# misc_rf.net
KiCad netlist of a schematic drawn in Altium Designer
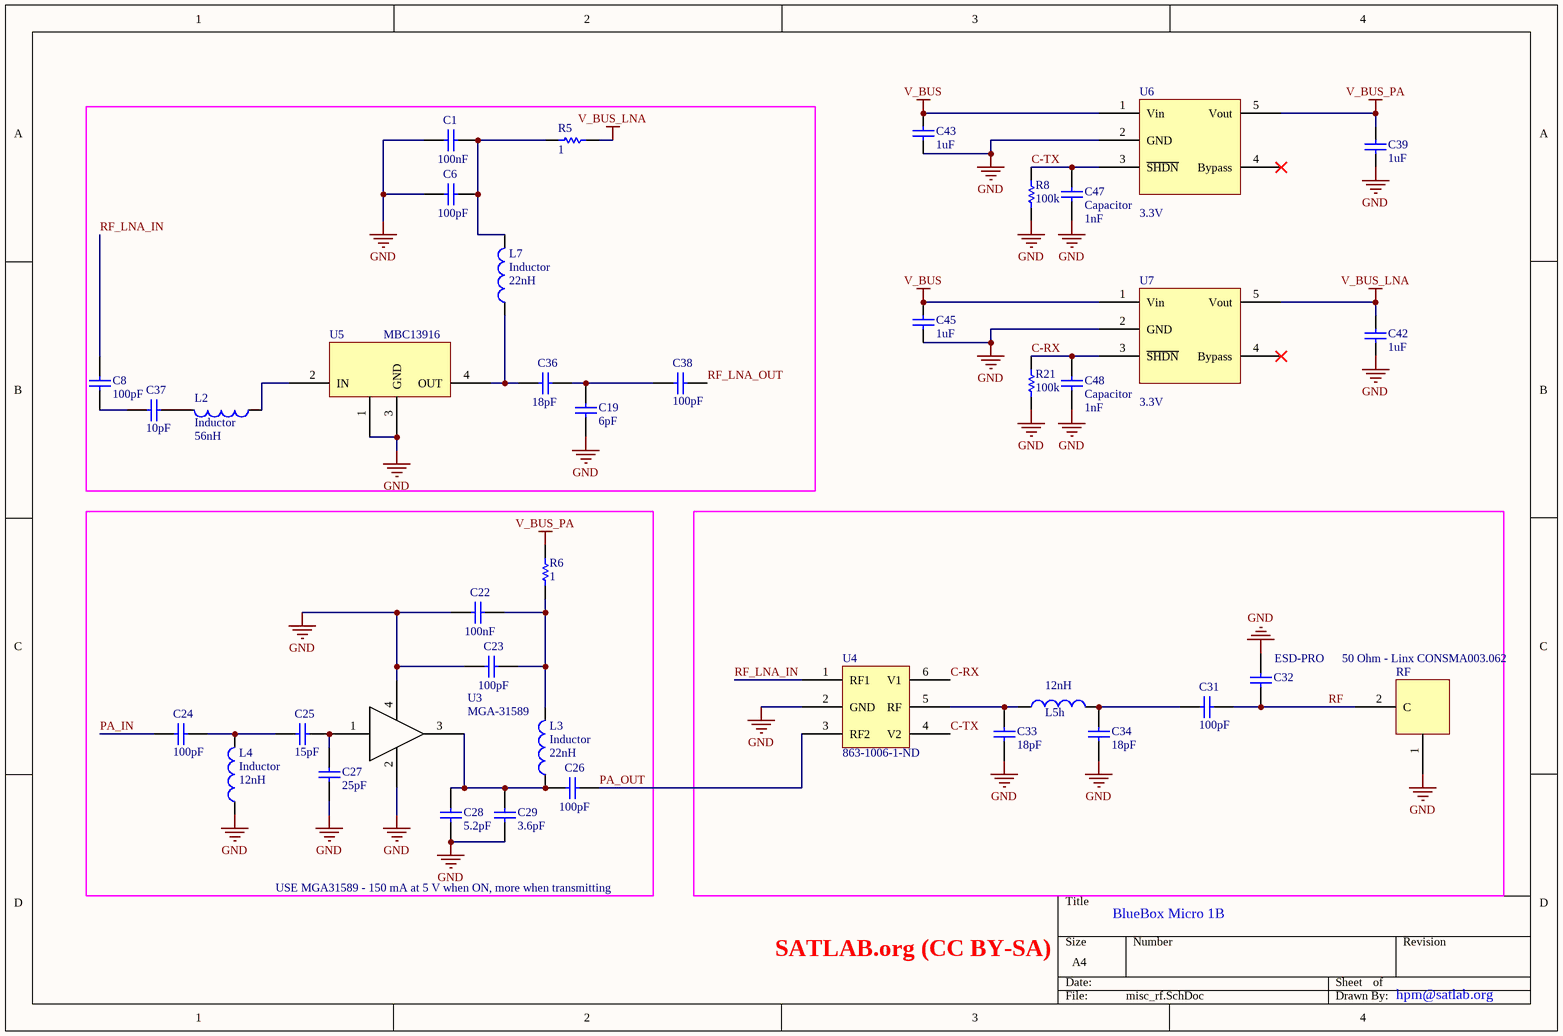
[diagram p0: misc_rf.SchDoc]

(export (version "E")
  (design (tool "Eeschema 10.0.6"))
  (components
    (comp (ref "C1")
      (value "100nF")
      (footprint "C06")
      (description "Capacitor (Semiconductor SIM Model)")
      (fields (field (name "Comment") "Cap Semi") (field (name "PUBLISHER") "Altium Limited"))
      (libsource (lib "common") (part "Capacitor"))
    )
    (comp (ref "C6")
      (value "100pF")
      (footprint "C06")
      (description "Capacitor (Semiconductor SIM Model)")
      (fields (field (name "Comment") "Cap Semi") (field (name "PUBLISHER") "Altium Limited"))
      (libsource (lib "common") (part "Capacitor"))
    )
    (comp (ref "C8")
      (value "100pF")
      (footprint "C06")
      (description "Capacitor (Semiconductor SIM Model)")
      (fields (field (name "Comment") "Cap Semi") (field (name "PUBLISHER") "Altium Limited"))
      (libsource (lib "common") (part "Capacitor"))
    )
    (comp (ref "C19")
      (value "6pF")
      (footprint "C06")
      (description "Capacitor (Semiconductor SIM Model)")
      (fields (field (name "Comment") "Cap Semi") (field (name "PUBLISHER") "Altium Limited"))
      (libsource (lib "common") (part "Capacitor"))
    )
    (comp (ref "C22")
      (value "100nF")
      (footprint "C06")
      (description "Capacitor (Semiconductor SIM Model)")
      (fields (field (name "Comment") "Cap Semi") (field (name "PUBLISHER") "Altium Limited"))
      (libsource (lib "common") (part "Capacitor"))
    )
    (comp (ref "C23")
      (value "100pF")
      (footprint "C06")
      (description "Capacitor (Semiconductor SIM Model)")
      (fields (field (name "Comment") "Cap Semi") (field (name "PUBLISHER") "Altium Limited"))
      (libsource (lib "common") (part "Capacitor"))
    )
    (comp (ref "C24")
      (value "100pF")
      (footprint "C06")
      (description "Capacitor (Semiconductor SIM Model)")
      (fields (field (name "Comment") "Cap Semi") (field (name "PUBLISHER") "Altium Limited"))
      (libsource (lib "common") (part "Capacitor"))
    )
    (comp (ref "C25")
      (value "15pF")
      (footprint "C06")
      (description "Capacitor (Semiconductor SIM Model)")
      (fields (field (name "Comment") "Cap Semi") (field (name "PUBLISHER") "Altium Limited"))
      (libsource (lib "common") (part "Capacitor"))
    )
    (comp (ref "C26")
      (value "100pF")
      (footprint "C06")
      (description "Capacitor (Semiconductor SIM Model)")
      (fields (field (name "Comment") "Cap Semi") (field (name "PUBLISHER") "Altium Limited"))
      (libsource (lib "common") (part "Capacitor"))
    )
    (comp (ref "C27")
      (value "25pF")
      (footprint "C06")
      (description "Capacitor (Semiconductor SIM Model)")
      (fields (field (name "Comment") "Cap Semi") (field (name "PUBLISHER") "Altium Limited"))
      (libsource (lib "common") (part "Capacitor"))
    )
    (comp (ref "C28")
      (value "5.2pF")
      (footprint "C06")
      (description "Capacitor (Semiconductor SIM Model)")
      (fields (field (name "Comment") "Cap Semi") (field (name "PUBLISHER") "Altium Limited"))
      (libsource (lib "common") (part "Capacitor"))
    )
    (comp (ref "C29")
      (value "3.6pF")
      (footprint "C06")
      (description "Capacitor (Semiconductor SIM Model)")
      (fields (field (name "Comment") "Cap Semi") (field (name "PUBLISHER") "Altium Limited"))
      (libsource (lib "common") (part "Capacitor"))
    )
    (comp (ref "C31")
      (value "100pF")
      (footprint "C06")
      (description "Capacitor, standard")
      (fields (field (name "Comment") "Capacitor"))
      (libsource (lib "common") (part "Capacitor"))
    )
    (comp (ref "C32")
      (value "ESD-PRO")
      (footprint "C06")
      (description "Capacitor, standard")
      (fields (field (name "Comment") "Capacitor"))
      (libsource (lib "common") (part "Capacitor"))
    )
    (comp (ref "C33")
      (value "18pF")
      (footprint "C06")
      (description "Capacitor (Semiconductor SIM Model)")
      (fields (field (name "Comment") "Cap Semi") (field (name "PUBLISHER") "Altium Limited"))
      (libsource (lib "common") (part "Capacitor"))
    )
    (comp (ref "C34")
      (value "18pF")
      (footprint "C06")
      (description "Capacitor (Semiconductor SIM Model)")
      (fields (field (name "Comment") "Cap Semi") (field (name "PUBLISHER") "Altium Limited"))
      (libsource (lib "common") (part "Capacitor"))
    )
    (comp (ref "C36")
      (value "18pF")
      (footprint "C06")
      (description "Capacitor (Semiconductor SIM Model)")
      (fields (field (name "Comment") "Cap Semi") (field (name "PUBLISHER") "Altium Limited"))
      (libsource (lib "common") (part "Capacitor"))
    )
    (comp (ref "C37")
      (value "10pF")
      (footprint "C06")
      (description "Capacitor (Semiconductor SIM Model)")
      (fields (field (name "Comment") "Cap Semi") (field (name "PUBLISHER") "Altium Limited"))
      (libsource (lib "common") (part "Capacitor"))
    )
    (comp (ref "C38")
      (value "100pF")
      (footprint "C06")
      (description "Capacitor (Semiconductor SIM Model)")
      (fields (field (name "Comment") "Cap Semi") (field (name "PUBLISHER") "Altium Limited"))
      (libsource (lib "common") (part "Capacitor"))
    )
    (comp (ref "C39")
      (value "1uF")
      (footprint "C06")
      (description "Capacitor, standard")
      (fields (field (name "Comment") "Capacitor"))
      (libsource (lib "AAUSAT3 AVR") (part "Capacitor"))
    )
    (comp (ref "C42")
      (value "1uF")
      (footprint "C06")
      (description "Capacitor, standard")
      (fields (field (name "Comment") "Capacitor"))
      (libsource (lib "AAUSAT3 AVR") (part "Capacitor"))
    )
    (comp (ref "C43")
      (value "1uF")
      (footprint "C06")
      (description "Capacitor, standard")
      (fields (field (name "Comment") "Capacitor"))
      (libsource (lib "AAUSAT3 AVR") (part "Capacitor"))
    )
    (comp (ref "C45")
      (value "1uF")
      (footprint "C06")
      (description "Capacitor, standard")
      (fields (field (name "Comment") "Capacitor"))
      (libsource (lib "AAUSAT3 AVR") (part "Capacitor"))
    )
    (comp (ref "C47")
      (value "Capacitor")
      (footprint "C06")
      (description "Capacitor, standard")
      (fields (field (name "ALTIUM_VALUE") "1nF"))
      (libsource (lib "common") (part "Capacitor"))
    )
    (comp (ref "C48")
      (value "Capacitor")
      (footprint "C06")
      (description "Capacitor, standard")
      (fields (field (name "ALTIUM_VALUE") "1nF"))
      (libsource (lib "common") (part "Capacitor"))
    )
    (comp (ref "L2")
      (value "Inductor")
      (footprint "C06")
      (fields (field (name "ALTIUM_VALUE") "56nH") (field (name "PUBLISHER") "<HP>"))
      (libsource (lib "common") (part "Inductor"))
    )
    (comp (ref "L3")
      (value "Inductor")
      (footprint "C06")
      (fields (field (name "ALTIUM_VALUE") "22nH") (field (name "PUBLISHER") "<HP>"))
      (libsource (lib "common") (part "Inductor"))
    )
    (comp (ref "L4")
      (value "Inductor")
      (footprint "C06")
      (fields (field (name "ALTIUM_VALUE") "12nH") (field (name "PUBLISHER") "<HP>"))
      (libsource (lib "common") (part "Inductor"))
    )
    (comp (ref "L5h")
      (value "12nH")
      (footprint "C06")
      (fields (field (name "Comment") "Inductor") (field (name "PUBLISHER") "<HP>"))
      (libsource (lib "common") (part "Inductor"))
    )
    (comp (ref "L7")
      (value "Inductor")
      (footprint "C06")
      (fields (field (name "ALTIUM_VALUE") "22nH") (field (name "PUBLISHER") "<HP>"))
      (libsource (lib "common") (part "Inductor"))
    )
    (comp (ref "R5")
      (value "1")
      (footprint "R06")
      (description "Resistor")
      (fields (field (name "BY") "Troels Jessen") (field (name "USERNAME") "tjessen"))
      (libsource (lib "common") (part "Resistor"))
    )
    (comp (ref "R6")
      (value "1")
      (footprint "R06")
      (description "Resistor")
      (fields (field (name "BY") "Troels Jessen") (field (name "USERNAME") "tjessen"))
      (libsource (lib "common") (part "Resistor"))
    )
    (comp (ref "R8")
      (value "100k")
      (footprint "R06")
      (description "Resistor")
      (fields (field (name "BY") "Troels Jessen") (field (name "USERNAME") "tjessen"))
      (libsource (lib "AAUSAT3 AVR") (part "Resistor"))
    )
    (comp (ref "R21")
      (value "100k")
      (footprint "R06")
      (description "Resistor")
      (fields (field (name "BY") "Troels Jessen") (field (name "USERNAME") "tjessen"))
      (libsource (lib "AAUSAT3 AVR") (part "Resistor"))
    )
    (comp (ref "RF")
      (value "50 Ohm - Linx CONSMA003.062")
      (footprint "sma-egde")
      (description "Linx CONSMA003.062  -  SMA Female Edge Mount for 1.6 mm PCB")
      (libsource (lib "Schlib1") (part "SMA_BOARD_EGDE"))
    )
    (comp (ref "U3")
      (value "MGA-31589")
      (footprint "SOT-223B-small")
      (description "0.5 W High Gain Driver Amplifier")
      (libsource (lib "Schlib1") (part "MGA-31589"))
    )
    (comp (ref "U4")
      (value "AS193-73")
      (footprint "SOT95P280X145-6N")
      (description "PHEMT GaAs IC High-Linearity 3 V  Control SPDT Switch 0.1–2.5 GHz")
      (fields (field (name "SUPPLIER PART NUMBER 1") "863-1006-1-ND") (field (name "BY") "HP"))
      (libsource (lib "common") (part "AS193-73"))
    )
    (comp (ref "U5") (value "MBC13916") (footprint "MBC13916") (libsource (lib "Schlib1") (part "MBC13916")))
    (comp (ref "U6")
      (value "~")
      (footprint "SOT23")
      (description "Voltage regulater from Microchip")
      (fields (field (name "VOLTAGE") "3.3V"))
      (libsource (lib "uhf") (part "TC1185"))
    )
    (comp (ref "U7")
      (value "~")
      (footprint "SOT23")
      (description "Voltage regulater from Microchip")
      (fields (field (name "VOLTAGE") "3.3V"))
      (libsource (lib "uhf") (part "TC1185"))
    )
  )
  (nets
    (net (code "1") (name "/C-RX") (class "Default")
      (node (ref "C48") (pin "1") (pinfunction "1_1") (pintype "passive"))
      (node (ref "R21") (pin "2") (pinfunction "2_2") (pintype "passive"))
      (node (ref "U4") (pin "6") (pinfunction "V1_6") (pintype "passive"))
      (node (ref "U7") (pin "3") (pinfunction "~{SHDN}_3") (pintype "passive"))
    )
    (net (code "2") (name "/C-TX") (class "Default")
      (node (ref "C47") (pin "1") (pinfunction "1_1") (pintype "passive"))
      (node (ref "R8") (pin "2") (pinfunction "2_2") (pintype "passive"))
      (node (ref "U4") (pin "4") (pinfunction "V2_4") (pintype "passive"))
      (node (ref "U6") (pin "3") (pinfunction "~{SHDN}_3") (pintype "passive"))
    )
    (net (code "3") (name "/PA_IN") (class "Default")
      (node (ref "C24") (pin "1") (pinfunction "1_1") (pintype "passive"))
    )
    (net (code "4") (name "/PA_OUT") (class "Default")
      (node (ref "C26") (pin "1") (pinfunction "1_1") (pintype "passive"))
      (node (ref "U4") (pin "3") (pinfunction "RF2_3") (pintype "passive"))
    )
    (net (code "5") (name "/RF") (class "Default")
      (node (ref "C31") (pin "1") (pinfunction "1_1") (pintype "passive"))
      (node (ref "C32") (pin "2") (pinfunction "2_2") (pintype "passive"))
      (node (ref "RF") (pin "2") (pinfunction "C_2") (pintype "passive"))
    )
    (net (code "6") (name "/RF_LNA_IN") (class "Default")
      (node (ref "C8") (pin "1") (pinfunction "1_1") (pintype "passive"))
      (node (ref "U4") (pin "1") (pinfunction "RF1_1") (pintype "passive"))
    )
    (net (code "7") (name "/RF_LNA_OUT") (class "Default")
      (node (ref "C38") (pin "2") (pinfunction "2_2") (pintype "passive"))
    )
    (net (code "8") (name "GND") (class "Default")
      (node (ref "C1") (pin "2") (pinfunction "2_2") (pintype "passive"))
      (node (ref "C19") (pin "2") (pinfunction "2_2") (pintype "passive"))
      (node (ref "C22") (pin "2") (pinfunction "2_2") (pintype "passive"))
      (node (ref "C23") (pin "2") (pinfunction "2_2") (pintype "passive"))
      (node (ref "C27") (pin "1") (pinfunction "1_1") (pintype "passive"))
      (node (ref "C28") (pin "2") (pinfunction "2_2") (pintype "passive"))
      (node (ref "C29") (pin "2") (pinfunction "2_2") (pintype "passive"))
      (node (ref "C32") (pin "1") (pinfunction "1_1") (pintype "passive"))
      (node (ref "C33") (pin "2") (pinfunction "2_2") (pintype "passive"))
      (node (ref "C34") (pin "2") (pinfunction "2_2") (pintype "passive"))
      (node (ref "C39") (pin "1") (pinfunction "1_1") (pintype "passive"))
      (node (ref "C42") (pin "1") (pinfunction "1_1") (pintype "passive"))
      (node (ref "C43") (pin "1") (pinfunction "1_1") (pintype "passive"))
      (node (ref "C45") (pin "1") (pinfunction "1_1") (pintype "passive"))
      (node (ref "C47") (pin "2") (pinfunction "2_2") (pintype "passive"))
      (node (ref "C48") (pin "2") (pinfunction "2_2") (pintype "passive"))
      (node (ref "C6") (pin "2") (pinfunction "2_2") (pintype "passive"))
      (node (ref "L4") (pin "1") (pinfunction "1_1") (pintype "passive"))
      (node (ref "R21") (pin "1") (pinfunction "1_1") (pintype "passive"))
      (node (ref "R8") (pin "1") (pinfunction "1_1") (pintype "passive"))
      (node (ref "RF") (pin "1") (pinfunction "GND_1") (pintype "passive"))
      (node (ref "U3") (pin "2") (pinfunction "GND_2") (pintype "passive"))
      (node (ref "U3") (pin "4") (pinfunction "GND_4") (pintype "passive"))
      (node (ref "U4") (pin "2") (pinfunction "GND_2") (pintype "power_in"))
      (node (ref "U5") (pin "1") (pinfunction "GND_1") (pintype "passive"))
      (node (ref "U5") (pin "3") (pinfunction "GND_3") (pintype "passive"))
      (node (ref "U6") (pin "2") (pinfunction "GND_2") (pintype "passive"))
      (node (ref "U7") (pin "2") (pinfunction "GND_2") (pintype "passive"))
    )
    (net (code "9") (name "Net-(C1-Pad1)") (class "Default")
      (node (ref "C1") (pin "1") (pinfunction "1_1") (pintype "passive"))
      (node (ref "C6") (pin "1") (pinfunction "1_1") (pintype "passive"))
      (node (ref "L7") (pin "2") (pinfunction "2_2") (pintype "passive"))
      (node (ref "R5") (pin "1") (pinfunction "1_1") (pintype "passive"))
    )
    (net (code "10") (name "Net-(C19-Pad1)") (class "Default")
      (node (ref "C19") (pin "1") (pinfunction "1_1") (pintype "passive"))
      (node (ref "C36") (pin "1") (pinfunction "1_1") (pintype "passive"))
      (node (ref "C38") (pin "1") (pinfunction "1_1") (pintype "passive"))
    )
    (net (code "11") (name "Net-(C22-Pad1)") (class "Default")
      (node (ref "C22") (pin "1") (pinfunction "1_1") (pintype "passive"))
      (node (ref "C23") (pin "1") (pinfunction "1_1") (pintype "passive"))
      (node (ref "L3") (pin "2") (pinfunction "2_2") (pintype "passive"))
      (node (ref "R6") (pin "1") (pinfunction "1_1") (pintype "passive"))
    )
    (net (code "12") (name "Net-(C24-Pad2)") (class "Default")
      (node (ref "C24") (pin "2") (pinfunction "2_2") (pintype "passive"))
      (node (ref "C25") (pin "1") (pinfunction "1_1") (pintype "passive"))
      (node (ref "L4") (pin "2") (pinfunction "2_2") (pintype "passive"))
    )
    (net (code "13") (name "Net-(C31-Pad2)") (class "Default")
      (node (ref "C31") (pin "2") (pinfunction "2_2") (pintype "passive"))
      (node (ref "C34") (pin "1") (pinfunction "1_1") (pintype "passive"))
      (node (ref "L5h") (pin "2") (pinfunction "2_2") (pintype "passive"))
    )
    (net (code "14") (name "Net-(C37-Pad1)") (class "Default")
      (node (ref "C37") (pin "1") (pinfunction "1_1") (pintype "passive"))
      (node (ref "C8") (pin "2") (pinfunction "2_2") (pintype "passive"))
    )
    (net (code "15") (name "Net-(C37-Pad2)") (class "Default")
      (node (ref "C37") (pin "2") (pinfunction "2_2") (pintype "passive"))
      (node (ref "L2") (pin "2") (pinfunction "2_2") (pintype "passive"))
    )
    (net (code "16") (name "Net-(U3-RF_IN)") (class "Default")
      (node (ref "C25") (pin "2") (pinfunction "2_2") (pintype "passive"))
      (node (ref "C27") (pin "2") (pinfunction "2_2") (pintype "passive"))
      (node (ref "U3") (pin "1") (pinfunction "RF_IN_1") (pintype "passive"))
    )
    (net (code "17") (name "Net-(U3-RF_OUT)") (class "Default")
      (node (ref "C26") (pin "2") (pinfunction "2_2") (pintype "passive"))
      (node (ref "C28") (pin "1") (pinfunction "1_1") (pintype "passive"))
      (node (ref "C29") (pin "1") (pinfunction "1_1") (pintype "passive"))
      (node (ref "L3") (pin "1") (pinfunction "1_1") (pintype "passive"))
      (node (ref "U3") (pin "3") (pinfunction "RF_OUT_3") (pintype "passive"))
    )
    (net (code "18") (name "Net-(U4-RF)") (class "Default")
      (node (ref "C33") (pin "1") (pinfunction "1_1") (pintype "passive"))
      (node (ref "L5h") (pin "1") (pinfunction "1_1") (pintype "passive"))
      (node (ref "U4") (pin "5") (pinfunction "RF_5") (pintype "passive"))
    )
    (net (code "19") (name "Net-(U5-IN)") (class "Default")
      (node (ref "L2") (pin "1") (pinfunction "1_1") (pintype "passive"))
      (node (ref "U5") (pin "2") (pinfunction "IN_2") (pintype "passive"))
    )
    (net (code "20") (name "Net-(U5-OUT)") (class "Default")
      (node (ref "C36") (pin "2") (pinfunction "2_2") (pintype "passive"))
      (node (ref "L7") (pin "1") (pinfunction "1_1") (pintype "passive"))
      (node (ref "U5") (pin "4") (pinfunction "OUT_4") (pintype "passive"))
    )
    (net (code "21") (name "V_BUS") (class "Default")
      (node (ref "C43") (pin "2") (pinfunction "2_2") (pintype "passive"))
      (node (ref "C45") (pin "2") (pinfunction "2_2") (pintype "passive"))
      (node (ref "U6") (pin "1") (pinfunction "Vin_1") (pintype "passive"))
      (node (ref "U7") (pin "1") (pinfunction "Vin_1") (pintype "passive"))
    )
    (net (code "22") (name "V_BUS_LNA") (class "Default")
      (node (ref "C42") (pin "2") (pinfunction "2_2") (pintype "passive"))
      (node (ref "R5") (pin "2") (pinfunction "2_2") (pintype "passive"))
      (node (ref "U7") (pin "5") (pinfunction "Vout_5") (pintype "passive"))
    )
    (net (code "23") (name "V_BUS_PA") (class "Default")
      (node (ref "C39") (pin "2") (pinfunction "2_2") (pintype "passive"))
      (node (ref "R6") (pin "2") (pinfunction "2_2") (pintype "passive"))
      (node (ref "U6") (pin "5") (pinfunction "Vout_5") (pintype "passive"))
    )
    (net (code "24") (name "unconnected-(U6-Bypass-Pad4)") (class "Default")
      (node (ref "U6") (pin "4") (pinfunction "Bypass_4") (pintype "passive+no_connect"))
    )
    (net (code "25") (name "unconnected-(U7-Bypass-Pad4)") (class "Default")
      (node (ref "U7") (pin "4") (pinfunction "Bypass_4") (pintype "passive+no_connect"))
    )
  )
)
